# SensorDSC.net
KiCad netlist of a schematic drawn in Altium Designer
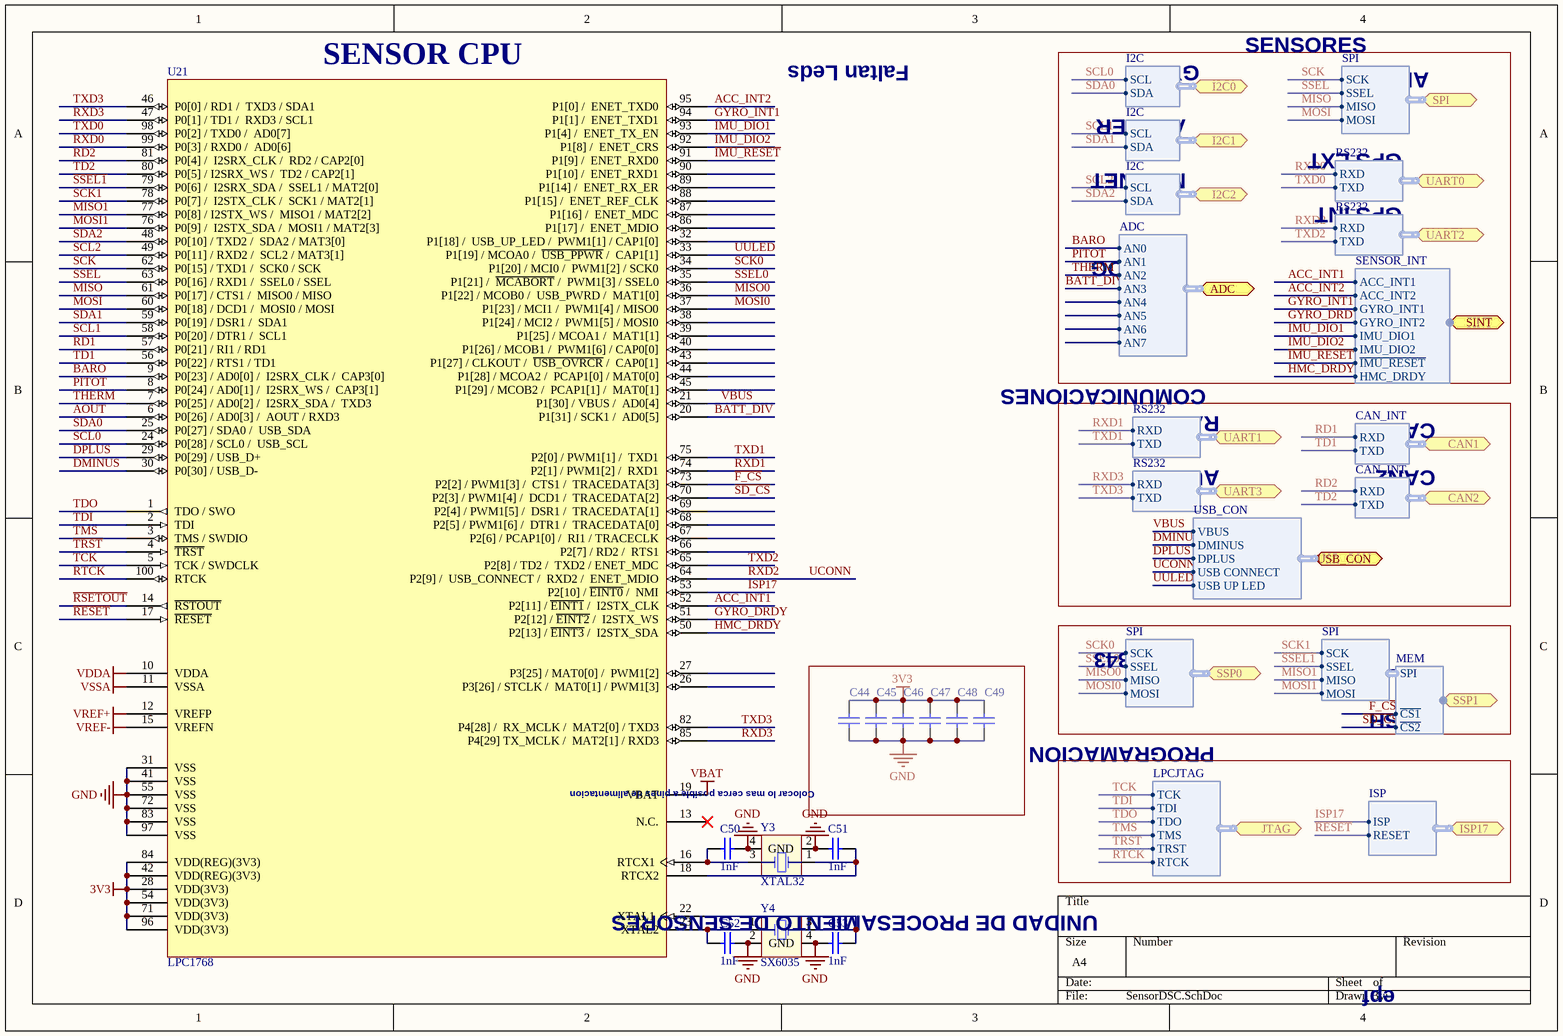
[diagram p0: SensorDSC.SchDoc]

(export (version "E")
  (design (tool "Eeschema 10.0.6"))
  (components
    (comp (ref "C44") (value "Capacitor") (footprint "CAP0402") (libsource (lib "epf") (part "Cap")))
    (comp (ref "C45") (value "Capacitor") (footprint "CAP0402") (libsource (lib "epf") (part "Cap")))
    (comp (ref "C46") (value "Capacitor") (footprint "CAP0402") (libsource (lib "epf") (part "Cap")))
    (comp (ref "C47") (value "Capacitor") (footprint "CAP0402") (libsource (lib "epf") (part "Cap")))
    (comp (ref "C48") (value "Capacitor") (footprint "CAP0402") (libsource (lib "epf") (part "Cap")))
    (comp (ref "C49") (value "Capacitor") (footprint "CAP0402") (libsource (lib "epf") (part "Cap")))
    (comp (ref "C50")
      (value "1nF")
      (footprint "CAP0402")
      (fields (field (name "Comment") "Capacitor"))
      (libsource (lib "epf") (part "Cap"))
    )
    (comp (ref "C51")
      (value "1nF")
      (footprint "CAP0402")
      (fields (field (name "Comment") "Capacitor"))
      (libsource (lib "epf") (part "Cap"))
    )
    (comp (ref "C52")
      (value "1nF")
      (footprint "CAP0402")
      (fields (field (name "Comment") "Capacitor"))
      (libsource (lib "epf") (part "Cap"))
    )
    (comp (ref "C53")
      (value "1nF")
      (footprint "CAP0402")
      (fields (field (name "Comment") "Capacitor"))
      (libsource (lib "epf") (part "Cap"))
    )
    (comp (ref "U21")
      (value "LPC1768")
      (footprint "SOT407-1 LPC1768")
      (description "ARM CortexM3 512K Flash, 64k RAM, CAN, USB, Ethernet, DAC")
      (fields (field (name "PUBLISHER") "Altium Limited"))
      (libsource (lib "epf") (part "LPC1768FBD100"))
    )
    (comp (ref "Y3")
      (value "XTAL32")
      (footprint "XTAL32")
      (description "Crystal Oscillator")
      (fields (field (name "PUBLISHER") "Altium Limited"))
      (libsource (lib "epf") (part "XTAL32"))
    )
    (comp (ref "Y4") (value "SX6035") (footprint "SX6035") (libsource (lib "epf") (part "XTAL_SX6035")))
  )
  (nets
    (net (code "11") (name "/ACC_INT1") (class "Default")
      (node (ref "U21") (pin "52") (pinfunction "P2[11]_/_~{EINT1}_/__I2STX_CLK_52") (pintype "bidirectional"))
    )
    (net (code "12") (name "/ACC_INT2") (class "Default")
      (node (ref "U21") (pin "95") (pinfunction "P1[0]_/__ENET_TXD0_95") (pintype "bidirectional"))
    )
    (net (code "13") (name "/AOUT") (class "Default")
      (node (ref "U21") (pin "6") (pinfunction "P0[26]_/_AD0[3]_/__AOUT_/_RXD3_6") (pintype "bidirectional"))
    )
    (net (code "14") (name "/BARO") (class "Default")
      (node (ref "U21") (pin "9") (pinfunction "P0[23]_/_AD0[0]_/__I2SRX_CLK_/__CAP3[0]_9") (pintype "bidirectional"))
    )
    (net (code "15") (name "/BATT_DIV") (class "Default")
      (node (ref "U21") (pin "20") (pinfunction "P1[31]_/_SCK1_/__AD0[5]_20") (pintype "bidirectional"))
    )
    (net (code "16") (name "/DMINUS") (class "Default")
      (node (ref "U21") (pin "30") (pinfunction "P0[30]_/_USB_D-_30") (pintype "bidirectional"))
    )
    (net (code "17") (name "/DPLUS") (class "Default")
      (node (ref "U21") (pin "29") (pinfunction "P0[29]_/_USB_D+_29") (pintype "bidirectional"))
    )
    (net (code "18") (name "/F_CS") (class "Default")
      (node (ref "U21") (pin "73") (pinfunction "P2[2]_/_PWM1[3]_/__CTS1_/__TRACEDATA[3]_73") (pintype "bidirectional"))
    )
    (net (code "19") (name "/GYRO_DRDY") (class "Default")
      (node (ref "U21") (pin "51") (pinfunction "P2[12]_/_~{EINT2}_/__I2STX_WS_51") (pintype "bidirectional"))
    )
    (net (code "20") (name "/GYRO_INT1") (class "Default")
      (node (ref "U21") (pin "94") (pinfunction "P1[1]_/__ENET_TXD1_94") (pintype "bidirectional"))
    )
    (net (code "21") (name "/HMC_DRDY") (class "Default")
      (node (ref "U21") (pin "50") (pinfunction "P2[13]_/_~{EINT3}_/__I2STX_SDA_50") (pintype "bidirectional"))
    )
    (net (code "22") (name "/IMU_DIO1") (class "Default")
      (node (ref "U21") (pin "93") (pinfunction "P1[4]_/__ENET_TX_EN_93") (pintype "bidirectional"))
    )
    (net (code "23") (name "/IMU_DIO2") (class "Default")
      (node (ref "U21") (pin "92") (pinfunction "P1[8]_/__ENET_CRS_92") (pintype "bidirectional"))
    )
    (net (code "24") (name "/IMU_RESET") (class "Default")
      (node (ref "U21") (pin "91") (pinfunction "P1[9]_/__ENET_RXD0_91") (pintype "bidirectional"))
    )
    (net (code "25") (name "/ISP17") (class "Default")
      (node (ref "U21") (pin "53") (pinfunction "P2[10]_/_~{EINT0}_/__NMI_53") (pintype "bidirectional"))
    )
    (net (code "26") (name "/MISO") (class "Default")
      (node (ref "U21") (pin "61") (pinfunction "P0[17]_/_CTS1_/__MISO0_/_MISO_61") (pintype "bidirectional"))
    )
    (net (code "27") (name "/MISO0") (class "Default")
      (node (ref "U21") (pin "36") (pinfunction "P1[22]_/_MCOB0_/__USB_PWRD_/__MAT1[0]_36") (pintype "bidirectional"))
    )
    (net (code "28") (name "/MISO1") (class "Default")
      (node (ref "U21") (pin "77") (pinfunction "P0[8]_/_I2STX_WS_/__MISO1_/_MAT2[2]_77") (pintype "bidirectional"))
    )
    (net (code "29") (name "/MOSI") (class "Default")
      (node (ref "U21") (pin "60") (pinfunction "P0[18]_/_DCD1_/__MOSI0_/_MOSI_60") (pintype "bidirectional"))
    )
    (net (code "30") (name "/MOSI0") (class "Default")
      (node (ref "U21") (pin "37") (pinfunction "P1[23]_/_MCI1_/__PWM1[4]_/_MISO0_37") (pintype "bidirectional"))
    )
    (net (code "31") (name "/MOSI1") (class "Default")
      (node (ref "U21") (pin "76") (pinfunction "P0[9]_/__I2STX_SDA_/__MOSI1_/_MAT2[3]_76") (pintype "bidirectional"))
    )
    (net (code "32") (name "/PITOT") (class "Default")
      (node (ref "U21") (pin "8") (pinfunction "P0[24]_/_AD0[1]_/__I2SRX_WS_/__CAP3[1]_8") (pintype "bidirectional"))
    )
    (net (code "33") (name "/RD1") (class "Default")
      (node (ref "U21") (pin "57") (pinfunction "P0[21]_/_RI1_/_RD1_57") (pintype "bidirectional"))
    )
    (net (code "34") (name "/RD2") (class "Default")
      (node (ref "U21") (pin "81") (pinfunction "P0[4]_/__I2SRX_CLK_/__RD2_/_CAP2[0]_81") (pintype "bidirectional"))
    )
    (net (code "35") (name "/RESET") (class "Default")
      (node (ref "U21") (pin "17") (pinfunction "~{RESET}_17") (pintype "input"))
    )
    (net (code "36") (name "/RSETOUT") (class "Default")
      (node (ref "U21") (pin "14") (pinfunction "~{RSTOUT}_14") (pintype "output"))
    )
    (net (code "37") (name "/RTCK") (class "Default")
      (node (ref "U21") (pin "100") (pinfunction "RTCK_100") (pintype "bidirectional"))
    )
    (net (code "38") (name "/RXD0") (class "Default")
      (node (ref "U21") (pin "99") (pinfunction "P0[3]_/_RXD0_/__AD0[6]_99") (pintype "bidirectional"))
    )
    (net (code "39") (name "/RXD1") (class "Default")
      (node (ref "U21") (pin "74") (pinfunction "P2[1]_/_PWM1[2]_/__RXD1_74") (pintype "bidirectional"))
    )
    (net (code "40") (name "/RXD2") (class "Default")
      (node (ref "U21") (pin "64") (pinfunction "P2[9]_/__USB_CONNECT_/__RXD2_/__ENET_MDIO_64") (pintype "bidirectional"))
    )
    (net (code "41") (name "/RXD3") (class "Default")
      (node (ref "U21") (pin "47") (pinfunction "P0[1]_/_TD1_/__RXD3_/_SCL1_47") (pintype "bidirectional"))
      (node (ref "U21") (pin "85") (pinfunction "P4[29]_TX_MCLK_/__MAT2[1]_/_RXD3_85") (pintype "bidirectional"))
    )
    (net (code "42") (name "/SCK") (class "Default")
      (node (ref "U21") (pin "62") (pinfunction "P0[15]_/_TXD1_/__SCK0_/_SCK_62") (pintype "bidirectional"))
    )
    (net (code "43") (name "/SCK0") (class "Default")
      (node (ref "U21") (pin "34") (pinfunction "P1[20]_/_MCI0_/__PWM1[2]_/_SCK0_34") (pintype "bidirectional"))
    )
    (net (code "44") (name "/SCK1") (class "Default")
      (node (ref "U21") (pin "78") (pinfunction "P0[7]_/__I2STX_CLK_/__SCK1_/_MAT2[1]_78") (pintype "bidirectional"))
    )
    (net (code "45") (name "/SCL0") (class "Default")
      (node (ref "U21") (pin "24") (pinfunction "P0[28]_/_SCL0_/__USB_SCL_24") (pintype "bidirectional"))
    )
    (net (code "46") (name "/SCL1") (class "Default")
      (node (ref "U21") (pin "58") (pinfunction "P0[20]_/_DTR1_/__SCL1_58") (pintype "bidirectional"))
    )
    (net (code "47") (name "/SCL2") (class "Default")
      (node (ref "U21") (pin "49") (pinfunction "P0[11]_/_RXD2_/__SCL2_/_MAT3[1]_49") (pintype "bidirectional"))
    )
    (net (code "48") (name "/SDA0") (class "Default")
      (node (ref "U21") (pin "25") (pinfunction "P0[27]_/_SDA0_/__USB_SDA_25") (pintype "bidirectional"))
    )
    (net (code "49") (name "/SDA1") (class "Default")
      (node (ref "U21") (pin "59") (pinfunction "P0[19]_/_DSR1_/__SDA1_59") (pintype "bidirectional"))
    )
    (net (code "50") (name "/SDA2") (class "Default")
      (node (ref "U21") (pin "48") (pinfunction "P0[10]_/_TXD2_/__SDA2_/_MAT3[0]_48") (pintype "bidirectional"))
    )
    (net (code "51") (name "/SD_CS") (class "Default")
      (node (ref "U21") (pin "70") (pinfunction "P2[3]_/_PWM1[4]_/__DCD1_/__TRACEDATA[2]_70") (pintype "bidirectional"))
    )
    (net (code "52") (name "/SSEL") (class "Default")
      (node (ref "U21") (pin "63") (pinfunction "P0[16]_/_RXD1_/__SSEL0_/_SSEL_63") (pintype "bidirectional"))
    )
    (net (code "53") (name "/SSEL0") (class "Default")
      (node (ref "U21") (pin "35") (pinfunction "P1[21]_/__~{MCABORT}_/__PWM1[3]_/_SSEL0_35") (pintype "bidirectional"))
    )
    (net (code "54") (name "/SSEL1") (class "Default")
      (node (ref "U21") (pin "79") (pinfunction "P0[6]_/__I2SRX_SDA_/__SSEL1_/_MAT2[0]_79") (pintype "bidirectional"))
    )
    (net (code "56") (name "/TCK") (class "Default")
      (node (ref "U21") (pin "5") (pinfunction "TCK_/_SWDCLK_5") (pintype "input"))
    )
    (net (code "57") (name "/TD1") (class "Default")
      (node (ref "U21") (pin "56") (pinfunction "P0[22]_/_RTS1_/_TD1_56") (pintype "bidirectional"))
    )
    (net (code "58") (name "/TD2") (class "Default")
      (node (ref "U21") (pin "80") (pinfunction "P0[5]_/_I2SRX_WS_/__TD2_/_CAP2[1]_80") (pintype "bidirectional"))
    )
    (net (code "59") (name "/TDI") (class "Default")
      (node (ref "U21") (pin "2") (pinfunction "TDI_2") (pintype "input"))
    )
    (net (code "60") (name "/TDO") (class "Default")
      (node (ref "U21") (pin "1") (pinfunction "TDO_/_SWO_1") (pintype "output"))
    )
    (net (code "61") (name "/THERM") (class "Default")
      (node (ref "U21") (pin "7") (pinfunction "P0[25]_/_AD0[2]_/__I2SRX_SDA_/__TXD3_7") (pintype "bidirectional"))
    )
    (net (code "62") (name "/TMS") (class "Default")
      (node (ref "U21") (pin "3") (pinfunction "TMS_/_SWDIO_3") (pintype "bidirectional"))
    )
    (net (code "63") (name "/TRST") (class "Default")
      (node (ref "U21") (pin "4") (pinfunction "~{TRST}_4") (pintype "input"))
    )
    (net (code "64") (name "/TXD0") (class "Default")
      (node (ref "U21") (pin "98") (pinfunction "P0[2]_/_TXD0_/__AD0[7]_98") (pintype "bidirectional"))
    )
    (net (code "65") (name "/TXD1") (class "Default")
      (node (ref "U21") (pin "75") (pinfunction "P2[0]_/_PWM1[1]_/__TXD1_75") (pintype "bidirectional"))
    )
    (net (code "66") (name "/TXD2") (class "Default")
      (node (ref "U21") (pin "65") (pinfunction "P2[8]_/_TD2_/__TXD2_/_ENET_MDC_65") (pintype "bidirectional"))
    )
    (net (code "67") (name "/TXD3") (class "Default")
      (node (ref "U21") (pin "46") (pinfunction "P0[0]_/_RD1_/__TXD3_/_SDA1_46") (pintype "bidirectional"))
      (node (ref "U21") (pin "82") (pinfunction "P4[28]_/__RX_MCLK_/__MAT2[0]_/_TXD3_82") (pintype "bidirectional"))
    )
    (net (code "68") (name "/UULED") (class "Default")
      (node (ref "U21") (pin "33") (pinfunction "P1[19]_/_MCOA0_/__~{USB_PPWR}_/__CAP1[1]_33") (pintype "bidirectional"))
    )
    (net (code "69") (name "/VBUS") (class "Default")
      (node (ref "U21") (pin "21") (pinfunction "P1[30]_/_VBUS_/__AD0[4]_21") (pintype "bidirectional"))
    )
    (net (code "79") (name "3V3") (class "Default")
      (node (ref "C44") (pin "2") (pinfunction "2_2") (pintype "passive"))
      (node (ref "C45") (pin "2") (pinfunction "2_2") (pintype "passive"))
      (node (ref "C46") (pin "2") (pinfunction "2_2") (pintype "passive"))
      (node (ref "C47") (pin "2") (pinfunction "2_2") (pintype "passive"))
      (node (ref "C48") (pin "2") (pinfunction "2_2") (pintype "passive"))
      (node (ref "C49") (pin "2") (pinfunction "2_2") (pintype "passive"))
      (node (ref "U21") (pin "28") (pinfunction "VDD(3V3)_28") (pintype "power_in"))
      (node (ref "U21") (pin "42") (pinfunction "VDD(REG)(3V3)_42") (pintype "power_in"))
      (node (ref "U21") (pin "54") (pinfunction "VDD(3V3)_54") (pintype "power_in"))
      (node (ref "U21") (pin "71") (pinfunction "VDD(3V3)_71") (pintype "power_in"))
      (node (ref "U21") (pin "84") (pinfunction "VDD(REG)(3V3)_84") (pintype "power_in"))
      (node (ref "U21") (pin "96") (pinfunction "VDD(3V3)_96") (pintype "power_in"))
    )
    (net (code "80") (name "GND") (class "Default")
      (node (ref "C44") (pin "1") (pinfunction "1_1") (pintype "passive"))
      (node (ref "C45") (pin "1") (pinfunction "1_1") (pintype "passive"))
      (node (ref "C46") (pin "1") (pinfunction "1_1") (pintype "passive"))
      (node (ref "C47") (pin "1") (pinfunction "1_1") (pintype "passive"))
      (node (ref "C48") (pin "1") (pinfunction "1_1") (pintype "passive"))
      (node (ref "C49") (pin "1") (pinfunction "1_1") (pintype "passive"))
      (node (ref "C50") (pin "1") (pinfunction "1_1") (pintype "passive"))
      (node (ref "C51") (pin "2") (pinfunction "2_2") (pintype "passive"))
      (node (ref "C52") (pin "1") (pinfunction "1_1") (pintype "passive"))
      (node (ref "C53") (pin "2") (pinfunction "2_2") (pintype "passive"))
      (node (ref "U21") (pin "31") (pinfunction "VSS_31") (pintype "power_in"))
      (node (ref "U21") (pin "41") (pinfunction "VSS_41") (pintype "power_in"))
      (node (ref "U21") (pin "55") (pinfunction "VSS_55") (pintype "power_in"))
      (node (ref "U21") (pin "72") (pinfunction "VSS_72") (pintype "power_in"))
      (node (ref "U21") (pin "83") (pinfunction "VSS_83") (pintype "power_in"))
      (node (ref "U21") (pin "97") (pinfunction "VSS_97") (pintype "power_in"))
      (node (ref "Y3") (pin "2") (pinfunction "GND_2") (pintype "passive"))
      (node (ref "Y3") (pin "4") (pinfunction "GND_4") (pintype "passive"))
      (node (ref "Y4") (pin "2") (pinfunction "GND_2") (pintype "passive"))
      (node (ref "Y4") (pin "4") (pinfunction "GND_4") (pintype "passive"))
    )
    (net (code "81") (name "Net-(U21-RTCX1)") (class "Default")
      (node (ref "C50") (pin "2") (pinfunction "2_2") (pintype "passive"))
      (node (ref "U21") (pin "16") (pinfunction "RTCX1_16") (pintype "input"))
      (node (ref "Y3") (pin "3") (pinfunction "XTAL_3") (pintype "passive"))
    )
    (net (code "82") (name "Net-(U21-RTCX2)") (class "Default")
      (node (ref "C51") (pin "1") (pinfunction "1_1") (pintype "passive"))
      (node (ref "U21") (pin "18") (pinfunction "RTCX2_18") (pintype "passive"))
      (node (ref "Y3") (pin "1") (pinfunction "XTAL_1") (pintype "passive"))
    )
    (net (code "83") (name "Net-(U21-XTAL1)") (class "Default")
      (node (ref "C53") (pin "1") (pinfunction "1_1") (pintype "passive"))
      (node (ref "U21") (pin "22") (pinfunction "XTAL1_22") (pintype "input"))
      (node (ref "Y4") (pin "3") (pinfunction "XTAL_3") (pintype "passive"))
    )
    (net (code "84") (name "Net-(U21-XTAL2)") (class "Default")
      (node (ref "C52") (pin "2") (pinfunction "2_2") (pintype "passive"))
      (node (ref "U21") (pin "23") (pinfunction "XTAL2_23") (pintype "passive"))
      (node (ref "Y4") (pin "1") (pinfunction "XTAL_1") (pintype "passive"))
    )
    (net (code "85") (name "VBAT") (class "Default")
      (node (ref "U21") (pin "19") (pinfunction "VBAT_19") (pintype "power_in"))
    )
    (net (code "86") (name "VDDA") (class "Default")
      (node (ref "U21") (pin "10") (pinfunction "VDDA_10") (pintype "power_in"))
    )
    (net (code "87") (name "VREF+") (class "Default")
      (node (ref "U21") (pin "12") (pinfunction "VREFP_12") (pintype "power_in"))
    )
    (net (code "88") (name "VREF-") (class "Default")
      (node (ref "U21") (pin "15") (pinfunction "VREFN_15") (pintype "power_in"))
    )
    (net (code "89") (name "VSSA") (class "Default")
      (node (ref "U21") (pin "11") (pinfunction "VSSA_11") (pintype "power_in"))
    )
    (net (code "90") (name "unconnected-(U21-N.C.-Pad13)") (class "Default")
      (node (ref "U21") (pin "13") (pinfunction "N.C._13") (pintype "passive+no_connect"))
    )
    (net (code "91") (name "unconnected-(U21-P1[10]_{slash}__ENET_RXD1-Pad90)") (class "Default")
      (node (ref "U21") (pin "90") (pinfunction "P1[10]_/__ENET_RXD1_90") (pintype "bidirectional"))
    )
    (net (code "92") (name "unconnected-(U21-P1[14]_{slash}__ENET_RX_ER-Pad89)") (class "Default")
      (node (ref "U21") (pin "89") (pinfunction "P1[14]_/__ENET_RX_ER_89") (pintype "bidirectional"))
    )
    (net (code "93") (name "unconnected-(U21-P1[15]_{slash}__ENET_REF_CLK-Pad88)") (class "Default")
      (node (ref "U21") (pin "88") (pinfunction "P1[15]_/__ENET_REF_CLK_88") (pintype "bidirectional"))
    )
    (net (code "94") (name "unconnected-(U21-P1[16]_{slash}__ENET_MDC-Pad87)") (class "Default")
      (node (ref "U21") (pin "87") (pinfunction "P1[16]_/__ENET_MDC_87") (pintype "bidirectional"))
    )
    (net (code "95") (name "unconnected-(U21-P1[17]_{slash}__ENET_MDIO-Pad86)") (class "Default")
      (node (ref "U21") (pin "86") (pinfunction "P1[17]_/__ENET_MDIO_86") (pintype "bidirectional"))
    )
    (net (code "96") (name "unconnected-(U21-P1[18]_{slash}__USB_UP_LED_{slash}__PWM1[1]_{slash}_CAP1[0]-Pad32)") (class "Default")
      (node (ref "U21") (pin "32") (pinfunction "P1[18]_/__USB_UP_LED_/__PWM1[1]_/_CAP1[0]_32") (pintype "bidirectional"))
    )
    (net (code "97") (name "unconnected-(U21-P1[24]_{slash}_MCI2_{slash}__PWM1[5]_{slash}_MOSI0-Pad38)") (class "Default")
      (node (ref "U21") (pin "38") (pinfunction "P1[24]_/_MCI2_/__PWM1[5]_/_MOSI0_38") (pintype "bidirectional"))
    )
    (net (code "98") (name "unconnected-(U21-P1[25]_{slash}_MCOA1_{slash}__MAT1[1]-Pad39)") (class "Default")
      (node (ref "U21") (pin "39") (pinfunction "P1[25]_/_MCOA1_/__MAT1[1]_39") (pintype "bidirectional"))
    )
    (net (code "99") (name "unconnected-(U21-P1[26]_{slash}_MCOB1_{slash}__PWM1[6]_{slash}_CAP0[0]-Pad40)") (class "Default")
      (node (ref "U21") (pin "40") (pinfunction "P1[26]_/_MCOB1_/__PWM1[6]_/_CAP0[0]_40") (pintype "bidirectional"))
    )
    (net (code "100") (name "unconnected-(U21-P1[27]_{slash}_CLKOUT_{slash}__~{USB_OVRCR}_{slash}__CAP0[1]-Pad43)") (class "Default")
      (node (ref "U21") (pin "43") (pinfunction "P1[27]_/_CLKOUT_/__~{USB_OVRCR}_/__CAP0[1]_43") (pintype "bidirectional"))
    )
    (net (code "101") (name "unconnected-(U21-P1[28]_{slash}_MCOA2_{slash}__PCAP1[0]_{slash}_MAT0[0]-Pad44)") (class "Default")
      (node (ref "U21") (pin "44") (pinfunction "P1[28]_/_MCOA2_/__PCAP1[0]_/_MAT0[0]_44") (pintype "bidirectional"))
    )
    (net (code "102") (name "unconnected-(U21-P1[29]_{slash}_MCOB2_{slash}__PCAP1[1]_{slash}__MAT0[1]-Pad45)") (class "Default")
      (node (ref "U21") (pin "45") (pinfunction "P1[29]_/_MCOB2_/__PCAP1[1]_/__MAT0[1]_45") (pintype "bidirectional"))
    )
    (net (code "103") (name "unconnected-(U21-P2[4]_{slash}_PWM1[5]_{slash}__DSR1_{slash}__TRACEDATA[1]-Pad69)") (class "Default")
      (node (ref "U21") (pin "69") (pinfunction "P2[4]_/_PWM1[5]_/__DSR1_/__TRACEDATA[1]_69") (pintype "bidirectional"))
    )
    (net (code "104") (name "unconnected-(U21-P2[5]_{slash}_PWM1[6]_{slash}__DTR1_{slash}__TRACEDATA[0]-Pad68)") (class "Default")
      (node (ref "U21") (pin "68") (pinfunction "P2[5]_/_PWM1[6]_/__DTR1_/__TRACEDATA[0]_68") (pintype "bidirectional"))
    )
    (net (code "105") (name "unconnected-(U21-P2[6]_{slash}_PCAP1[0]_{slash}__RI1_{slash}_TRACECLK-Pad67)") (class "Default")
      (node (ref "U21") (pin "67") (pinfunction "P2[6]_/_PCAP1[0]_/__RI1_/_TRACECLK_67") (pintype "bidirectional"))
    )
    (net (code "106") (name "unconnected-(U21-P2[7]_{slash}_RD2_{slash}__RTS1-Pad66)") (class "Default")
      (node (ref "U21") (pin "66") (pinfunction "P2[7]_/_RD2_/__RTS1_66") (pintype "bidirectional"))
    )
    (net (code "107") (name "unconnected-(U21-P3[25]_{slash}_MAT0[0]_{slash}__PWM1[2]-Pad27)") (class "Default")
      (node (ref "U21") (pin "27") (pinfunction "P3[25]_/_MAT0[0]_/__PWM1[2]_27") (pintype "bidirectional"))
    )
    (net (code "108") (name "unconnected-(U21-P3[26]_{slash}_STCLK_{slash}__MAT0[1]_{slash}_PWM1[3]-Pad26)") (class "Default")
      (node (ref "U21") (pin "26") (pinfunction "P3[26]_/_STCLK_/__MAT0[1]_/_PWM1[3]_26") (pintype "bidirectional"))
    )
  )
)
